# MCP73871_Battery_charger.net
KiCad netlist of a schematic drawn in Altium Designer
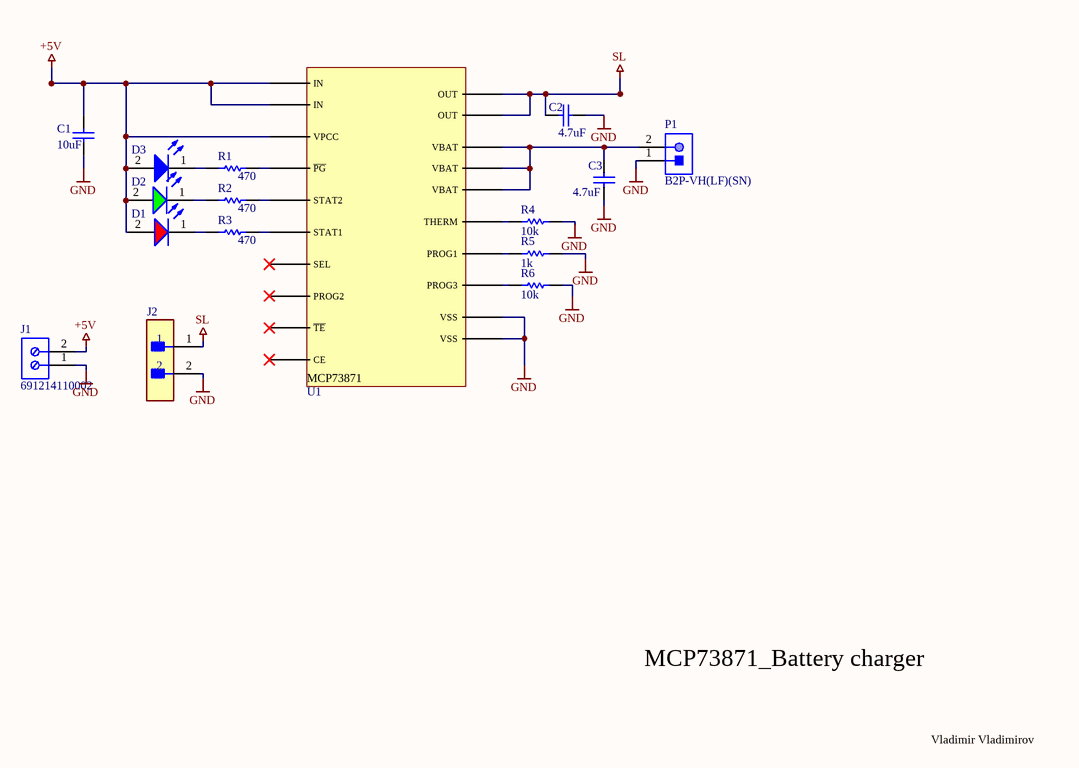
[diagram p0: MCP73871_Battery charger.SchDoc]

(export (version "E")
  (design (tool "Eeschema 10.0.6"))
  (components
    (comp (ref "C1")
      (value "10uF")
      (footprint "CAPC2013X145X50NL20T25")
      (description "Chip Capacitor, 10 uF, -20% to +80%, 10 V, -30 to 85 degC, 0805 (2012 Metric), RoHS, Tape and Reel")
      (fields (field (name "TOLERANCE") "-20%,+80%") (field (name "MANUFACTURER") "Yageo"))
      (libsource (lib "Altium Content Vault") (part "CAP-NP-2"))
    )
    (comp (ref "C2")
      (value "4.7uF")
      (footprint "CAPC2014X150X70ML20")
      (fields
        (field (name "PART NUMBER") "TACR475M010RTA")
        (field (name "MANUFACTURER") "AVX Interconnect / Elco")
      )
      (libsource (lib "Altium Content Vault") (part "CAP"))
    )
    (comp (ref "C3")
      (value "4.7uF")
      (footprint "CAPC2014X150X70ML20")
      (fields
        (field (name "PART NUMBER") "TACR475M010RTA")
        (field (name "MANUFACTURER") "AVX Interconnect / Elco")
      )
      (libsource (lib "Altium Content Vault") (part "CAP"))
    )
    (comp (ref "D1")
      (value "150120RS75000")
      (footprint "WL-SMCW_1206_150120xx75000")
      (libsource (lib "Altium Content Vault") (part "LED_Red_2A-1K"))
    )
    (comp (ref "D2")
      (value "150120GS75000")
      (footprint "WL-SMCW_1206_150120xx75000")
      (libsource (lib "Altium Content Vault") (part "LED_Green_2A-1K"))
    )
    (comp (ref "D3")
      (value "150120BS75000")
      (footprint "WL-SMCW_1206_150120xx75000")
      (libsource (lib "Altium Content Vault") (part "LED_Blue_2A-1K"))
    )
    (comp (ref "J1")
      (value "691214110002")
      (footprint "691214110002")
      (fields (field (name "VOLTAGE") "300V"))
      (libsource (lib "Altium Content Vault") (part "TBL - 1R - 02P - Screw"))
    )
    (comp (ref "J2")
      (value "TMM-102-01-L-S")
      (footprint "FP-TMM-102-01-L-S-MFG")
      (description "CONN HEADER VERT 2POS 2MM")
      (libsource (lib "Altium Content Vault") (part "3bc925449376181038e59eaffc5286c"))
    )
    (comp (ref "P1")
      (value "B2P-VH(LF)(SN)")
      (footprint "JST-B2P-VH(LF)(SN)_V")
      (fields (field (name "MANUFACTURER") "JST"))
      (libsource (lib "PGMEE Burgas") (part "CN-1P-M-R2"))
    )
    (comp (ref "R1")
      (value "470")
      (footprint "RESC2013X50X30NL20T20")
      (fields (field (name "MANUFACTURER") "Vishay Dale") (field (name "PART NUMBER") "CRCW0805470RFKEA"))
      (libsource (lib "Altium Content Vault") (part "RES"))
    )
    (comp (ref "R2")
      (value "470")
      (footprint "RESC2013X50X30NL20T20")
      (fields (field (name "MANUFACTURER") "Vishay Dale") (field (name "PART NUMBER") "CRCW0805470RFKEA"))
      (libsource (lib "Altium Content Vault") (part "RES"))
    )
    (comp (ref "R3")
      (value "470")
      (footprint "RESC2013X50X30NL20T20")
      (fields (field (name "MANUFACTURER") "Vishay Dale") (field (name "PART NUMBER") "CRCW0805470RFKEA"))
      (libsource (lib "Altium Content Vault") (part "RES"))
    )
    (comp (ref "R4")
      (value "10k")
      (footprint "RESC1005X40X25ML05T05")
      (fields (field (name "MANUFACTURER") "Panasonic") (field (name "PART NUMBER") "ERT-J0EM103J"))
      (libsource (lib "Altium Content Vault") (part "RES"))
    )
    (comp (ref "R5")
      (value "1k")
      (footprint "RESC2013X55X40ML15T20")
      (fields (field (name "MANUFACTURER") "Vishay Dale") (field (name "PART NUMBER") "TNPW08051K00BEEA"))
      (libsource (lib "Altium Content Vault") (part "RES"))
    )
    (comp (ref "R6")
      (value "10k")
      (footprint "RESC2013X60X40NL20T25_A")
      (fields (field (name "TOLERANCE") "0.1%") (field (name "MANUFACTURER") "Panasonic"))
      (libsource (lib "Altium Content Vault") (part "RES-2"))
    )
    (comp (ref "U1")
      (value "MCP73871")
      (footprint "MCP73871")
      (description "Li-Ion/Li-Polymer Battery Charge")
      (libsource (lib "MCP73871_12.05.24") (part "MCP73871"))
    )
  )
  (nets
    (net (code "1") (name "+5V") (class "Default")
      (node (ref "C1") (pin "2") (pinfunction "2_2") (pintype "passive"))
      (node (ref "D1") (pin "2") (pinfunction "A_2") (pintype "passive"))
      (node (ref "D2") (pin "2") (pinfunction "A_2") (pintype "passive"))
      (node (ref "D3") (pin "2") (pinfunction "A_2") (pintype "passive"))
      (node (ref "J1") (pin "2") (pinfunction "2_2") (pintype "passive"))
      (node (ref "U1") (pin "18") (pinfunction "IN_18") (pintype "passive"))
      (node (ref "U1") (pin "19") (pinfunction "IN_19") (pintype "passive"))
      (node (ref "U1") (pin "2") (pinfunction "VPCC_2") (pintype "passive"))
    )
    (net (code "2") (name "GND") (class "Default")
      (node (ref "C1") (pin "1") (pinfunction "1_1") (pintype "passive"))
      (node (ref "C2") (pin "1") (pinfunction "1_1") (pintype "passive"))
      (node (ref "C3") (pin "1") (pinfunction "1_1") (pintype "passive"))
      (node (ref "J1") (pin "1") (pinfunction "1_1") (pintype "passive"))
      (node (ref "J2") (pin "2") (pinfunction "2_2") (pintype "passive"))
      (node (ref "P1") (pin "1") (pinfunction "1_1") (pintype "passive"))
      (node (ref "R4") (pin "2") (pinfunction "2_2") (pintype "passive"))
      (node (ref "R5") (pin "2") (pinfunction "2_2") (pintype "passive"))
      (node (ref "R6") (pin "2") (pinfunction "2_2") (pintype "passive"))
      (node (ref "U1") (pin "10") (pinfunction "VSS_10") (pintype "passive"))
      (node (ref "U1") (pin "11") (pinfunction "VSS_11") (pintype "passive"))
    )
    (net (code "3") (name "Net-(C3-Pad2)") (class "Default")
      (node (ref "C3") (pin "2") (pinfunction "2_2") (pintype "passive"))
      (node (ref "P1") (pin "2") (pinfunction "2_2") (pintype "passive"))
      (node (ref "U1") (pin "14") (pinfunction "VBAT_14") (pintype "passive"))
      (node (ref "U1") (pin "15") (pinfunction "VBAT_15") (pintype "passive"))
      (node (ref "U1") (pin "16") (pinfunction "VBAT_16") (pintype "passive"))
    )
    (net (code "4") (name "Net-(D1-K)") (class "Default")
      (node (ref "D1") (pin "1") (pinfunction "K_1") (pintype "passive"))
      (node (ref "R3") (pin "1") (pinfunction "1_1") (pintype "passive"))
    )
    (net (code "5") (name "Net-(D2-K)") (class "Default")
      (node (ref "D2") (pin "1") (pinfunction "K_1") (pintype "passive"))
      (node (ref "R2") (pin "1") (pinfunction "1_1") (pintype "passive"))
    )
    (net (code "6") (name "Net-(D3-K)") (class "Default")
      (node (ref "D3") (pin "1") (pinfunction "K_1") (pintype "passive"))
      (node (ref "R1") (pin "1") (pinfunction "1_1") (pintype "passive"))
    )
    (net (code "7") (name "Net-(U1-PROG1)") (class "Default")
      (node (ref "R5") (pin "1") (pinfunction "1_1") (pintype "passive"))
      (node (ref "U1") (pin "13") (pinfunction "PROG1_13") (pintype "passive"))
    )
    (net (code "8") (name "Net-(U1-PROG3)") (class "Default")
      (node (ref "R6") (pin "1") (pinfunction "1_1") (pintype "passive"))
      (node (ref "U1") (pin "12") (pinfunction "PROG3_12") (pintype "passive"))
    )
    (net (code "9") (name "Net-(U1-STAT1)") (class "Default")
      (node (ref "R3") (pin "2") (pinfunction "2_2") (pintype "passive"))
      (node (ref "U1") (pin "8") (pinfunction "STAT1_8") (pintype "passive"))
    )
    (net (code "10") (name "Net-(U1-STAT2)") (class "Default")
      (node (ref "R2") (pin "2") (pinfunction "2_2") (pintype "passive"))
      (node (ref "U1") (pin "7") (pinfunction "STAT2_7") (pintype "passive"))
    )
    (net (code "11") (name "Net-(U1-THERM)") (class "Default")
      (node (ref "R4") (pin "1") (pinfunction "1_1") (pintype "passive"))
      (node (ref "U1") (pin "5") (pinfunction "THERM_5") (pintype "passive"))
    )
    (net (code "12") (name "Net-(U1-~{PG})") (class "Default")
      (node (ref "R1") (pin "2") (pinfunction "2_2") (pintype "passive"))
      (node (ref "U1") (pin "6") (pinfunction "~{PG}_6") (pintype "passive"))
    )
    (net (code "13") (name "SL") (class "Default")
      (node (ref "C2") (pin "2") (pinfunction "2_2") (pintype "passive"))
      (node (ref "J2") (pin "1") (pinfunction "1_1") (pintype "passive"))
      (node (ref "U1") (pin "1") (pinfunction "OUT_1") (pintype "passive"))
      (node (ref "U1") (pin "20") (pinfunction "OUT_20") (pintype "passive"))
    )
    (net (code "14") (name "unconnected-(U1-CE-Pad17)") (class "Default")
      (node (ref "U1") (pin "17") (pinfunction "CE_17") (pintype "passive+no_connect"))
    )
    (net (code "15") (name "unconnected-(U1-PROG2-Pad4)") (class "Default")
      (node (ref "U1") (pin "4") (pinfunction "PROG2_4") (pintype "passive+no_connect"))
    )
    (net (code "16") (name "unconnected-(U1-SEL-Pad3)") (class "Default")
      (node (ref "U1") (pin "3") (pinfunction "SEL_3") (pintype "passive+no_connect"))
    )
    (net (code "17") (name "unconnected-(U1-~{TE}-Pad9)") (class "Default")
      (node (ref "U1") (pin "9") (pinfunction "~{TE}_9") (pintype "passive+no_connect"))
    )
  )
)
